# B142X.net
KiCad netlist of a schematic drawn in EAGLE
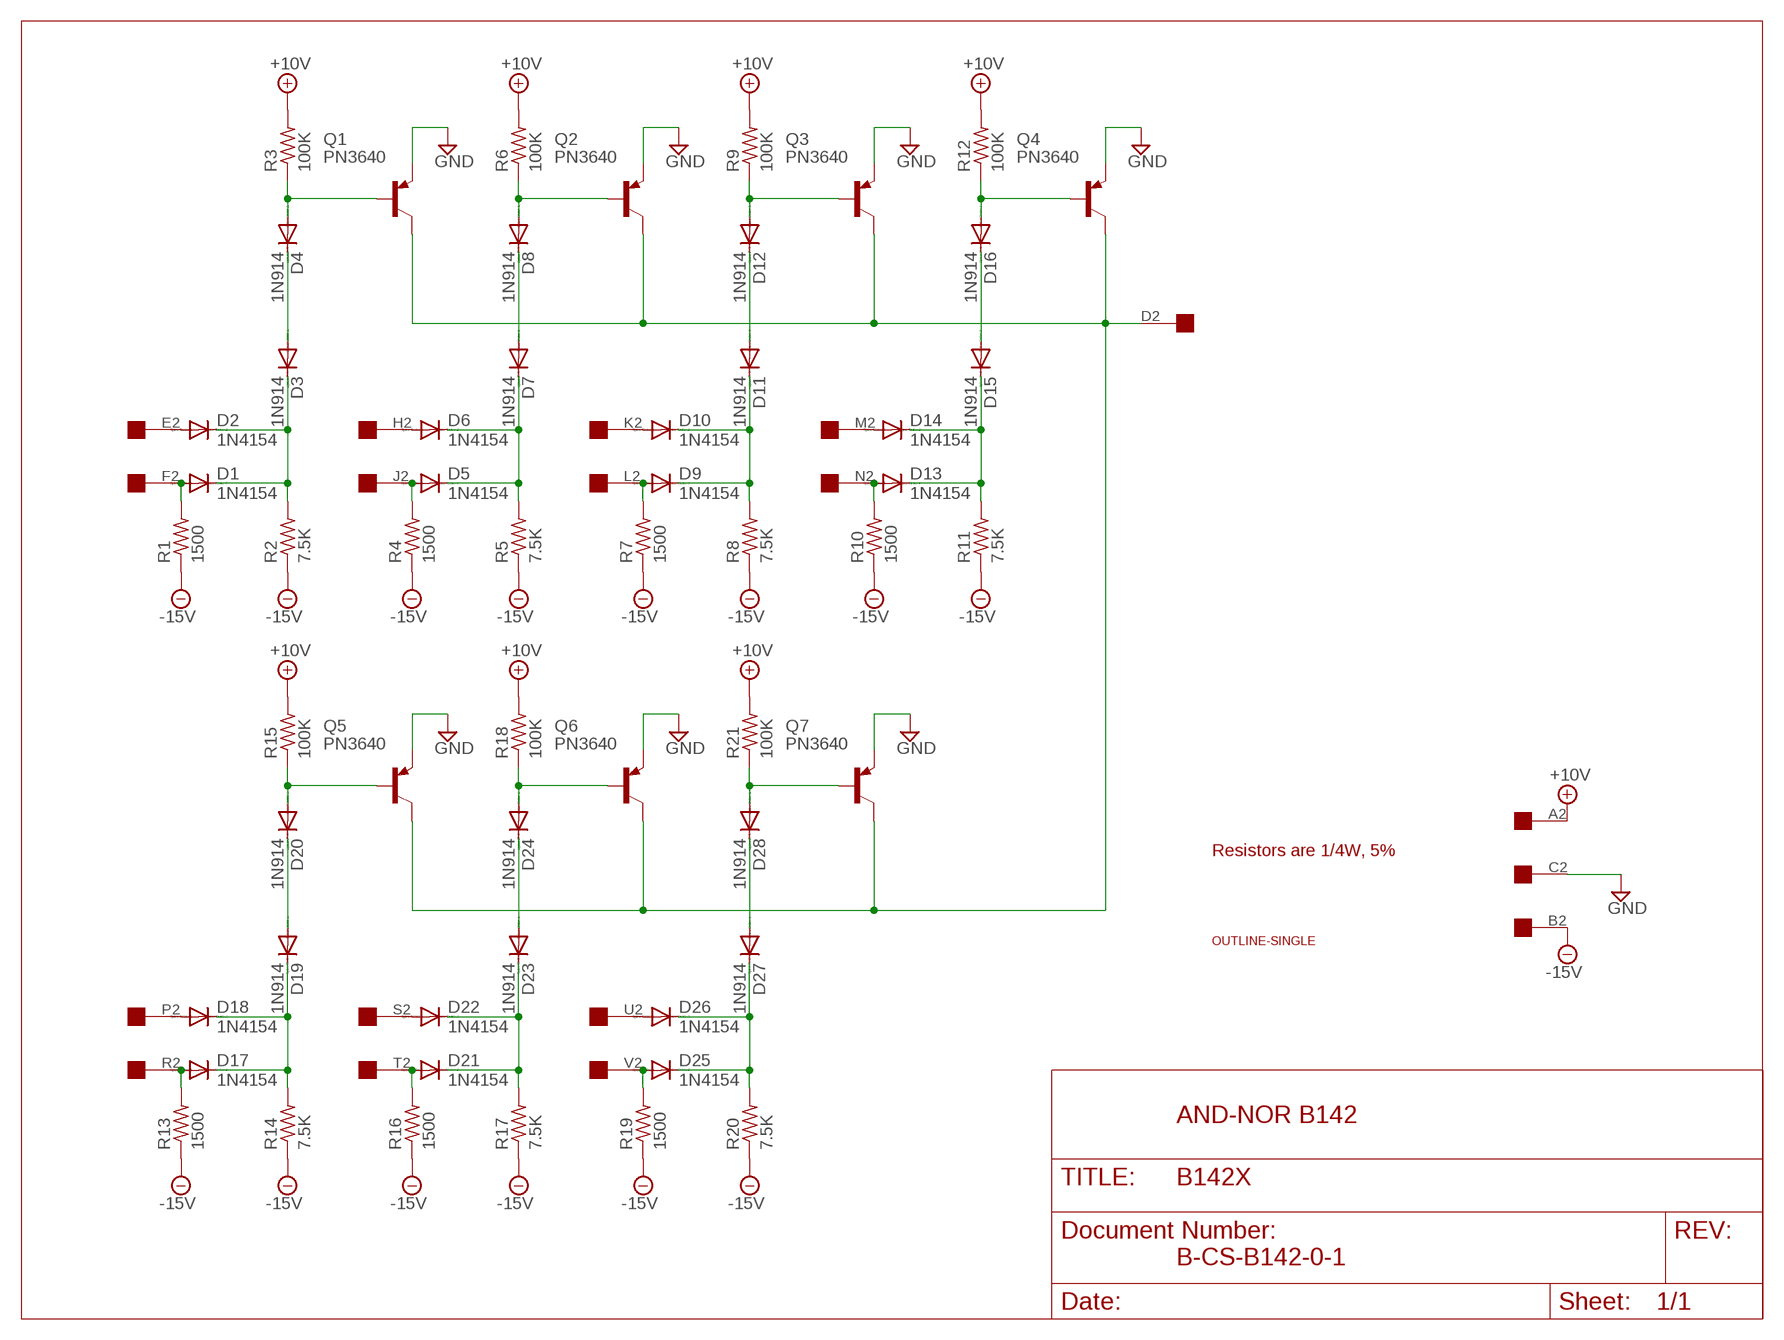
[diagram p0: schematic, sheet 1]

(export (version "E")
  (design (tool "Eeschema 10.0.6"))
  (components
    (comp (ref "D1")
      (value "1N4154")
      (footprint "eagle-import:DO35-10")
      (libsource (lib "eagle-import") (part "1N4148DO35-10"))
    )
    (comp (ref "D2")
      (value "1N4154")
      (footprint "eagle-import:DO35-10")
      (libsource (lib "eagle-import") (part "1N4148DO35-10"))
    )
    (comp (ref "D3")
      (value "1N914")
      (footprint "eagle-import:DO35-10")
      (libsource (lib "eagle-import") (part "1N4148DO35-10"))
    )
    (comp (ref "D4")
      (value "1N914")
      (footprint "eagle-import:DO35-10")
      (libsource (lib "eagle-import") (part "1N4148DO35-10"))
    )
    (comp (ref "D5")
      (value "1N4154")
      (footprint "eagle-import:DO35-10")
      (libsource (lib "eagle-import") (part "1N4148DO35-10"))
    )
    (comp (ref "D6")
      (value "1N4154")
      (footprint "eagle-import:DO35-10")
      (libsource (lib "eagle-import") (part "1N4148DO35-10"))
    )
    (comp (ref "D7")
      (value "1N914")
      (footprint "eagle-import:DO35-10")
      (libsource (lib "eagle-import") (part "1N4148DO35-10"))
    )
    (comp (ref "D8")
      (value "1N914")
      (footprint "eagle-import:DO35-10")
      (libsource (lib "eagle-import") (part "1N4148DO35-10"))
    )
    (comp (ref "D9")
      (value "1N4154")
      (footprint "eagle-import:DO35-10")
      (libsource (lib "eagle-import") (part "1N4148DO35-10"))
    )
    (comp (ref "D10")
      (value "1N4154")
      (footprint "eagle-import:DO35-10")
      (libsource (lib "eagle-import") (part "1N4148DO35-10"))
    )
    (comp (ref "D11")
      (value "1N914")
      (footprint "eagle-import:DO35-10")
      (libsource (lib "eagle-import") (part "1N4148DO35-10"))
    )
    (comp (ref "D12")
      (value "1N914")
      (footprint "eagle-import:DO35-10")
      (libsource (lib "eagle-import") (part "1N4148DO35-10"))
    )
    (comp (ref "D13")
      (value "1N4154")
      (footprint "eagle-import:DO35-10")
      (libsource (lib "eagle-import") (part "1N4148DO35-10"))
    )
    (comp (ref "D14")
      (value "1N4154")
      (footprint "eagle-import:DO35-10")
      (libsource (lib "eagle-import") (part "1N4148DO35-10"))
    )
    (comp (ref "D15")
      (value "1N914")
      (footprint "eagle-import:DO35-10")
      (libsource (lib "eagle-import") (part "1N4148DO35-10"))
    )
    (comp (ref "D16")
      (value "1N914")
      (footprint "eagle-import:DO35-10")
      (libsource (lib "eagle-import") (part "1N4148DO35-10"))
    )
    (comp (ref "D17")
      (value "1N4154")
      (footprint "eagle-import:DO35-10")
      (libsource (lib "eagle-import") (part "1N4148DO35-10"))
    )
    (comp (ref "D18")
      (value "1N4154")
      (footprint "eagle-import:DO35-10")
      (libsource (lib "eagle-import") (part "1N4148DO35-10"))
    )
    (comp (ref "D19")
      (value "1N914")
      (footprint "eagle-import:DO35-10")
      (libsource (lib "eagle-import") (part "1N4148DO35-10"))
    )
    (comp (ref "D20")
      (value "1N914")
      (footprint "eagle-import:DO35-10")
      (libsource (lib "eagle-import") (part "1N4148DO35-10"))
    )
    (comp (ref "D21")
      (value "1N4154")
      (footprint "eagle-import:DO35-10")
      (libsource (lib "eagle-import") (part "1N4148DO35-10"))
    )
    (comp (ref "D22")
      (value "1N4154")
      (footprint "eagle-import:DO35-10")
      (libsource (lib "eagle-import") (part "1N4148DO35-10"))
    )
    (comp (ref "D23")
      (value "1N914")
      (footprint "eagle-import:DO35-10")
      (libsource (lib "eagle-import") (part "1N4148DO35-10"))
    )
    (comp (ref "D24")
      (value "1N914")
      (footprint "eagle-import:DO35-10")
      (libsource (lib "eagle-import") (part "1N4148DO35-10"))
    )
    (comp (ref "D25")
      (value "1N4154")
      (footprint "eagle-import:DO35-10")
      (libsource (lib "eagle-import") (part "1N4148DO35-10"))
    )
    (comp (ref "D26")
      (value "1N4154")
      (footprint "eagle-import:DO35-10")
      (libsource (lib "eagle-import") (part "1N4148DO35-10"))
    )
    (comp (ref "D27")
      (value "1N914")
      (footprint "eagle-import:DO35-10")
      (libsource (lib "eagle-import") (part "1N4148DO35-10"))
    )
    (comp (ref "D28")
      (value "1N914")
      (footprint "eagle-import:DO35-10")
      (libsource (lib "eagle-import") (part "1N4148DO35-10"))
    )
    (comp (ref "Q1")
      (value "PN3640")
      (footprint "eagle-import:TO39")
      (libsource (lib "eagle-import") (part "2N3637"))
    )
    (comp (ref "Q2")
      (value "PN3640")
      (footprint "eagle-import:TO39")
      (libsource (lib "eagle-import") (part "2N3637"))
    )
    (comp (ref "Q3")
      (value "PN3640")
      (footprint "eagle-import:TO39")
      (libsource (lib "eagle-import") (part "2N3637"))
    )
    (comp (ref "Q4")
      (value "PN3640")
      (footprint "eagle-import:TO39")
      (libsource (lib "eagle-import") (part "2N3637"))
    )
    (comp (ref "Q5")
      (value "PN3640")
      (footprint "eagle-import:TO39")
      (libsource (lib "eagle-import") (part "2N3637"))
    )
    (comp (ref "Q6")
      (value "PN3640")
      (footprint "eagle-import:TO39")
      (libsource (lib "eagle-import") (part "2N3637"))
    )
    (comp (ref "Q7")
      (value "PN3640")
      (footprint "eagle-import:TO39")
      (libsource (lib "eagle-import") (part "2N3637"))
    )
    (comp (ref "R1")
      (value "1500")
      (footprint "eagle-import:0207_10")
      (libsource (lib "eagle-import") (part "R-US_0207/10"))
    )
    (comp (ref "R2")
      (value "7.5K")
      (footprint "eagle-import:0207_10")
      (libsource (lib "eagle-import") (part "R-US_0207/10"))
    )
    (comp (ref "R3")
      (value "100K")
      (footprint "eagle-import:0207_10")
      (libsource (lib "eagle-import") (part "R-US_0207/10"))
    )
    (comp (ref "R4")
      (value "1500")
      (footprint "eagle-import:0207_10")
      (libsource (lib "eagle-import") (part "R-US_0207/10"))
    )
    (comp (ref "R5")
      (value "7.5K")
      (footprint "eagle-import:0207_10")
      (libsource (lib "eagle-import") (part "R-US_0207/10"))
    )
    (comp (ref "R6")
      (value "100K")
      (footprint "eagle-import:0207_10")
      (libsource (lib "eagle-import") (part "R-US_0207/10"))
    )
    (comp (ref "R7")
      (value "1500")
      (footprint "eagle-import:0207_10")
      (libsource (lib "eagle-import") (part "R-US_0207/10"))
    )
    (comp (ref "R8")
      (value "7.5K")
      (footprint "eagle-import:0207_10")
      (libsource (lib "eagle-import") (part "R-US_0207/10"))
    )
    (comp (ref "R9")
      (value "100K")
      (footprint "eagle-import:0207_10")
      (libsource (lib "eagle-import") (part "R-US_0207/10"))
    )
    (comp (ref "R10")
      (value "1500")
      (footprint "eagle-import:0207_10")
      (libsource (lib "eagle-import") (part "R-US_0207/10"))
    )
    (comp (ref "R11")
      (value "7.5K")
      (footprint "eagle-import:0207_10")
      (libsource (lib "eagle-import") (part "R-US_0207/10"))
    )
    (comp (ref "R12")
      (value "100K")
      (footprint "eagle-import:0207_10")
      (libsource (lib "eagle-import") (part "R-US_0207/10"))
    )
    (comp (ref "R13")
      (value "1500")
      (footprint "eagle-import:0207_10")
      (libsource (lib "eagle-import") (part "R-US_0207/10"))
    )
    (comp (ref "R14")
      (value "7.5K")
      (footprint "eagle-import:0207_10")
      (libsource (lib "eagle-import") (part "R-US_0207/10"))
    )
    (comp (ref "R15")
      (value "100K")
      (footprint "eagle-import:0207_10")
      (libsource (lib "eagle-import") (part "R-US_0207/10"))
    )
    (comp (ref "R16")
      (value "1500")
      (footprint "eagle-import:0207_10")
      (libsource (lib "eagle-import") (part "R-US_0207/10"))
    )
    (comp (ref "R17")
      (value "7.5K")
      (footprint "eagle-import:0207_10")
      (libsource (lib "eagle-import") (part "R-US_0207/10"))
    )
    (comp (ref "R18")
      (value "100K")
      (footprint "eagle-import:0207_10")
      (libsource (lib "eagle-import") (part "R-US_0207/10"))
    )
    (comp (ref "R19")
      (value "1500")
      (footprint "eagle-import:0207_10")
      (libsource (lib "eagle-import") (part "R-US_0207/10"))
    )
    (comp (ref "R20")
      (value "7.5K")
      (footprint "eagle-import:0207_10")
      (libsource (lib "eagle-import") (part "R-US_0207/10"))
    )
    (comp (ref "R21")
      (value "100K")
      (footprint "eagle-import:0207_10")
      (libsource (lib "eagle-import") (part "R-US_0207/10"))
    )
    (comp (ref "U$1")
      (value "OUTLINE-SINGLE")
      (footprint "eagle-import:SINGLE")
      (libsource (lib "eagle-import") (part "OUTLINE-SINGLE"))
    )
    (comp (ref "U$2")
      (value "EDGE-1")
      (footprint "eagle-import:EDGE-CON1")
      (libsource (lib "eagle-import") (part "EDGE-1"))
    )
  )
  (nets
    (net (code "1") (name "+10V") (class "Default")
      (node (ref "R12") (pin "2") (pinfunction "2_2") (pintype "passive"))
      (node (ref "R15") (pin "2") (pinfunction "2_2") (pintype "passive"))
      (node (ref "R18") (pin "2") (pinfunction "2_2") (pintype "passive"))
      (node (ref "R21") (pin "2") (pinfunction "2_2") (pintype "passive"))
      (node (ref "R3") (pin "2") (pinfunction "2_2") (pintype "passive"))
      (node (ref "R6") (pin "2") (pinfunction "2_2") (pintype "passive"))
      (node (ref "R9") (pin "2") (pinfunction "2_2") (pintype "passive"))
      (node (ref "U$2") (pin "A2") (pinfunction "1_A2") (pintype "bidirectional"))
    )
    (net (code "2") (name "-15V") (class "Default")
      (node (ref "R1") (pin "1") (pinfunction "1_1") (pintype "passive"))
      (node (ref "R10") (pin "1") (pinfunction "1_1") (pintype "passive"))
      (node (ref "R11") (pin "1") (pinfunction "1_1") (pintype "passive"))
      (node (ref "R13") (pin "1") (pinfunction "1_1") (pintype "passive"))
      (node (ref "R14") (pin "1") (pinfunction "1_1") (pintype "passive"))
      (node (ref "R16") (pin "1") (pinfunction "1_1") (pintype "passive"))
      (node (ref "R17") (pin "1") (pinfunction "1_1") (pintype "passive"))
      (node (ref "R19") (pin "1") (pinfunction "1_1") (pintype "passive"))
      (node (ref "R2") (pin "1") (pinfunction "1_1") (pintype "passive"))
      (node (ref "R20") (pin "1") (pinfunction "1_1") (pintype "passive"))
      (node (ref "R4") (pin "1") (pinfunction "1_1") (pintype "passive"))
      (node (ref "R5") (pin "1") (pinfunction "1_1") (pintype "passive"))
      (node (ref "R7") (pin "1") (pinfunction "1_1") (pintype "passive"))
      (node (ref "R8") (pin "1") (pinfunction "1_1") (pintype "passive"))
      (node (ref "U$2") (pin "B2") (pinfunction "1_B2") (pintype "bidirectional"))
    )
    (net (code "3") (name "GND") (class "Default")
      (node (ref "Q1") (pin "1") (pinfunction "E_1") (pintype "passive"))
      (node (ref "Q2") (pin "1") (pinfunction "E_1") (pintype "passive"))
      (node (ref "Q3") (pin "1") (pinfunction "E_1") (pintype "passive"))
      (node (ref "Q4") (pin "1") (pinfunction "E_1") (pintype "passive"))
      (node (ref "Q5") (pin "1") (pinfunction "E_1") (pintype "passive"))
      (node (ref "Q6") (pin "1") (pinfunction "E_1") (pintype "passive"))
      (node (ref "Q7") (pin "1") (pinfunction "E_1") (pintype "passive"))
      (node (ref "U$2") (pin "C2") (pinfunction "1_C2") (pintype "bidirectional"))
    )
    (net (code "4") (name "Net-(D1-PadC)") (class "Default")
      (node (ref "D1") (pin "C") (pinfunction "C_C") (pintype "passive"))
      (node (ref "D2") (pin "C") (pinfunction "C_C") (pintype "passive"))
      (node (ref "D3") (pin "C") (pinfunction "C_C") (pintype "passive"))
      (node (ref "R2") (pin "2") (pinfunction "2_2") (pintype "passive"))
    )
    (net (code "5") (name "Net-(D3-PadA)") (class "Default")
      (node (ref "D3") (pin "A") (pinfunction "A_A") (pintype "passive"))
      (node (ref "D4") (pin "C") (pinfunction "C_C") (pintype "passive"))
    )
    (net (code "6") (name "Net-(D5-PadC)") (class "Default")
      (node (ref "D5") (pin "C") (pinfunction "C_C") (pintype "passive"))
      (node (ref "D6") (pin "C") (pinfunction "C_C") (pintype "passive"))
      (node (ref "D7") (pin "C") (pinfunction "C_C") (pintype "passive"))
      (node (ref "R5") (pin "2") (pinfunction "2_2") (pintype "passive"))
    )
    (net (code "7") (name "Net-(D7-PadA)") (class "Default")
      (node (ref "D7") (pin "A") (pinfunction "A_A") (pintype "passive"))
      (node (ref "D8") (pin "C") (pinfunction "C_C") (pintype "passive"))
    )
    (net (code "8") (name "Net-(D10-PadC)") (class "Default")
      (node (ref "D10") (pin "C") (pinfunction "C_C") (pintype "passive"))
      (node (ref "D11") (pin "C") (pinfunction "C_C") (pintype "passive"))
      (node (ref "D9") (pin "C") (pinfunction "C_C") (pintype "passive"))
      (node (ref "R8") (pin "2") (pinfunction "2_2") (pintype "passive"))
    )
    (net (code "9") (name "Net-(D11-PadA)") (class "Default")
      (node (ref "D11") (pin "A") (pinfunction "A_A") (pintype "passive"))
      (node (ref "D12") (pin "C") (pinfunction "C_C") (pintype "passive"))
    )
    (net (code "10") (name "Net-(D13-PadC)") (class "Default")
      (node (ref "D13") (pin "C") (pinfunction "C_C") (pintype "passive"))
      (node (ref "D14") (pin "C") (pinfunction "C_C") (pintype "passive"))
      (node (ref "D15") (pin "C") (pinfunction "C_C") (pintype "passive"))
      (node (ref "R11") (pin "2") (pinfunction "2_2") (pintype "passive"))
    )
    (net (code "11") (name "Net-(D15-PadA)") (class "Default")
      (node (ref "D15") (pin "A") (pinfunction "A_A") (pintype "passive"))
      (node (ref "D16") (pin "C") (pinfunction "C_C") (pintype "passive"))
    )
    (net (code "12") (name "Net-(D17-PadC)") (class "Default")
      (node (ref "D17") (pin "C") (pinfunction "C_C") (pintype "passive"))
      (node (ref "D18") (pin "C") (pinfunction "C_C") (pintype "passive"))
      (node (ref "D19") (pin "C") (pinfunction "C_C") (pintype "passive"))
      (node (ref "R14") (pin "2") (pinfunction "2_2") (pintype "passive"))
    )
    (net (code "13") (name "Net-(D19-PadA)") (class "Default")
      (node (ref "D19") (pin "A") (pinfunction "A_A") (pintype "passive"))
      (node (ref "D20") (pin "C") (pinfunction "C_C") (pintype "passive"))
    )
    (net (code "14") (name "Net-(D21-PadC)") (class "Default")
      (node (ref "D21") (pin "C") (pinfunction "C_C") (pintype "passive"))
      (node (ref "D22") (pin "C") (pinfunction "C_C") (pintype "passive"))
      (node (ref "D23") (pin "C") (pinfunction "C_C") (pintype "passive"))
      (node (ref "R17") (pin "2") (pinfunction "2_2") (pintype "passive"))
    )
    (net (code "15") (name "Net-(D23-PadA)") (class "Default")
      (node (ref "D23") (pin "A") (pinfunction "A_A") (pintype "passive"))
      (node (ref "D24") (pin "C") (pinfunction "C_C") (pintype "passive"))
    )
    (net (code "16") (name "Net-(D25-PadC)") (class "Default")
      (node (ref "D25") (pin "C") (pinfunction "C_C") (pintype "passive"))
      (node (ref "D26") (pin "C") (pinfunction "C_C") (pintype "passive"))
      (node (ref "D27") (pin "C") (pinfunction "C_C") (pintype "passive"))
      (node (ref "R20") (pin "2") (pinfunction "2_2") (pintype "passive"))
    )
    (net (code "17") (name "Net-(D27-PadA)") (class "Default")
      (node (ref "D27") (pin "A") (pinfunction "A_A") (pintype "passive"))
      (node (ref "D28") (pin "C") (pinfunction "C_C") (pintype "passive"))
    )
    (net (code "18") (name "Net-(Q1-B)") (class "Default")
      (node (ref "D4") (pin "A") (pinfunction "A_A") (pintype "passive"))
      (node (ref "Q1") (pin "2") (pinfunction "B_2") (pintype "passive"))
      (node (ref "R3") (pin "1") (pinfunction "1_1") (pintype "passive"))
    )
    (net (code "19") (name "Net-(Q1-C)") (class "Default")
      (node (ref "Q1") (pin "3") (pinfunction "C_3") (pintype "passive"))
      (node (ref "Q2") (pin "3") (pinfunction "C_3") (pintype "passive"))
      (node (ref "Q3") (pin "3") (pinfunction "C_3") (pintype "passive"))
      (node (ref "Q4") (pin "3") (pinfunction "C_3") (pintype "passive"))
      (node (ref "Q5") (pin "3") (pinfunction "C_3") (pintype "passive"))
      (node (ref "Q6") (pin "3") (pinfunction "C_3") (pintype "passive"))
      (node (ref "Q7") (pin "3") (pinfunction "C_3") (pintype "passive"))
      (node (ref "U$2") (pin "D2") (pinfunction "1_D2") (pintype "bidirectional"))
    )
    (net (code "20") (name "Net-(Q2-B)") (class "Default")
      (node (ref "D8") (pin "A") (pinfunction "A_A") (pintype "passive"))
      (node (ref "Q2") (pin "2") (pinfunction "B_2") (pintype "passive"))
      (node (ref "R6") (pin "1") (pinfunction "1_1") (pintype "passive"))
    )
    (net (code "21") (name "Net-(Q3-B)") (class "Default")
      (node (ref "D12") (pin "A") (pinfunction "A_A") (pintype "passive"))
      (node (ref "Q3") (pin "2") (pinfunction "B_2") (pintype "passive"))
      (node (ref "R9") (pin "1") (pinfunction "1_1") (pintype "passive"))
    )
    (net (code "22") (name "Net-(Q4-B)") (class "Default")
      (node (ref "D16") (pin "A") (pinfunction "A_A") (pintype "passive"))
      (node (ref "Q4") (pin "2") (pinfunction "B_2") (pintype "passive"))
      (node (ref "R12") (pin "1") (pinfunction "1_1") (pintype "passive"))
    )
    (net (code "23") (name "Net-(Q5-B)") (class "Default")
      (node (ref "D20") (pin "A") (pinfunction "A_A") (pintype "passive"))
      (node (ref "Q5") (pin "2") (pinfunction "B_2") (pintype "passive"))
      (node (ref "R15") (pin "1") (pinfunction "1_1") (pintype "passive"))
    )
    (net (code "24") (name "Net-(Q6-B)") (class "Default")
      (node (ref "D24") (pin "A") (pinfunction "A_A") (pintype "passive"))
      (node (ref "Q6") (pin "2") (pinfunction "B_2") (pintype "passive"))
      (node (ref "R18") (pin "1") (pinfunction "1_1") (pintype "passive"))
    )
    (net (code "25") (name "Net-(Q7-B)") (class "Default")
      (node (ref "D28") (pin "A") (pinfunction "A_A") (pintype "passive"))
      (node (ref "Q7") (pin "2") (pinfunction "B_2") (pintype "passive"))
      (node (ref "R21") (pin "1") (pinfunction "1_1") (pintype "passive"))
    )
    (net (code "26") (name "Net-(U$2E-1)") (class "Default")
      (node (ref "D2") (pin "A") (pinfunction "A_A") (pintype "passive"))
      (node (ref "U$2") (pin "E2") (pinfunction "1_E2") (pintype "bidirectional"))
    )
    (net (code "27") (name "Net-(U$2F-1)") (class "Default")
      (node (ref "D1") (pin "A") (pinfunction "A_A") (pintype "passive"))
      (node (ref "R1") (pin "2") (pinfunction "2_2") (pintype "passive"))
      (node (ref "U$2") (pin "F2") (pinfunction "1_F2") (pintype "bidirectional"))
    )
    (net (code "28") (name "Net-(U$2G-1)") (class "Default")
      (node (ref "D6") (pin "A") (pinfunction "A_A") (pintype "passive"))
      (node (ref "U$2") (pin "H2") (pinfunction "1_H2") (pintype "bidirectional"))
    )
    (net (code "29") (name "Net-(U$2H-1)") (class "Default")
      (node (ref "D5") (pin "A") (pinfunction "A_A") (pintype "passive"))
      (node (ref "R4") (pin "2") (pinfunction "2_2") (pintype "passive"))
      (node (ref "U$2") (pin "J2") (pinfunction "1_J2") (pintype "bidirectional"))
    )
    (net (code "30") (name "Net-(U$2I-1)") (class "Default")
      (node (ref "D10") (pin "A") (pinfunction "A_A") (pintype "passive"))
      (node (ref "U$2") (pin "K2") (pinfunction "1_K2") (pintype "bidirectional"))
    )
    (net (code "31") (name "Net-(U$2J-1)") (class "Default")
      (node (ref "D9") (pin "A") (pinfunction "A_A") (pintype "passive"))
      (node (ref "R7") (pin "2") (pinfunction "2_2") (pintype "passive"))
      (node (ref "U$2") (pin "L2") (pinfunction "1_L2") (pintype "bidirectional"))
    )
    (net (code "32") (name "Net-(U$2K-1)") (class "Default")
      (node (ref "D14") (pin "A") (pinfunction "A_A") (pintype "passive"))
      (node (ref "U$2") (pin "M2") (pinfunction "1_M2") (pintype "bidirectional"))
    )
    (net (code "33") (name "Net-(U$2L-1)") (class "Default")
      (node (ref "D13") (pin "A") (pinfunction "A_A") (pintype "passive"))
      (node (ref "R10") (pin "2") (pinfunction "2_2") (pintype "passive"))
      (node (ref "U$2") (pin "N2") (pinfunction "1_N2") (pintype "bidirectional"))
    )
    (net (code "34") (name "Net-(U$2M-1)") (class "Default")
      (node (ref "D18") (pin "A") (pinfunction "A_A") (pintype "passive"))
      (node (ref "U$2") (pin "P2") (pinfunction "1_P2") (pintype "bidirectional"))
    )
    (net (code "35") (name "Net-(U$2N-1)") (class "Default")
      (node (ref "D17") (pin "A") (pinfunction "A_A") (pintype "passive"))
      (node (ref "R13") (pin "2") (pinfunction "2_2") (pintype "passive"))
      (node (ref "U$2") (pin "R2") (pinfunction "1_R2") (pintype "bidirectional"))
    )
    (net (code "36") (name "Net-(U$2O-1)") (class "Default")
      (node (ref "D22") (pin "A") (pinfunction "A_A") (pintype "passive"))
      (node (ref "U$2") (pin "S2") (pinfunction "1_S2") (pintype "bidirectional"))
    )
    (net (code "37") (name "Net-(U$2P-1)") (class "Default")
      (node (ref "D21") (pin "A") (pinfunction "A_A") (pintype "passive"))
      (node (ref "R16") (pin "2") (pinfunction "2_2") (pintype "passive"))
      (node (ref "U$2") (pin "T2") (pinfunction "1_T2") (pintype "bidirectional"))
    )
    (net (code "38") (name "Net-(U$2Q-1)") (class "Default")
      (node (ref "D26") (pin "A") (pinfunction "A_A") (pintype "passive"))
      (node (ref "U$2") (pin "U2") (pinfunction "1_U2") (pintype "bidirectional"))
    )
    (net (code "39") (name "Net-(U$2R-1)") (class "Default")
      (node (ref "D25") (pin "A") (pinfunction "A_A") (pintype "passive"))
      (node (ref "R19") (pin "2") (pinfunction "2_2") (pintype "passive"))
      (node (ref "U$2") (pin "V2") (pinfunction "1_V2") (pintype "bidirectional"))
    )
  )
)
